# untitled.net
KiCad netlist of a schematic drawn in EAGLE
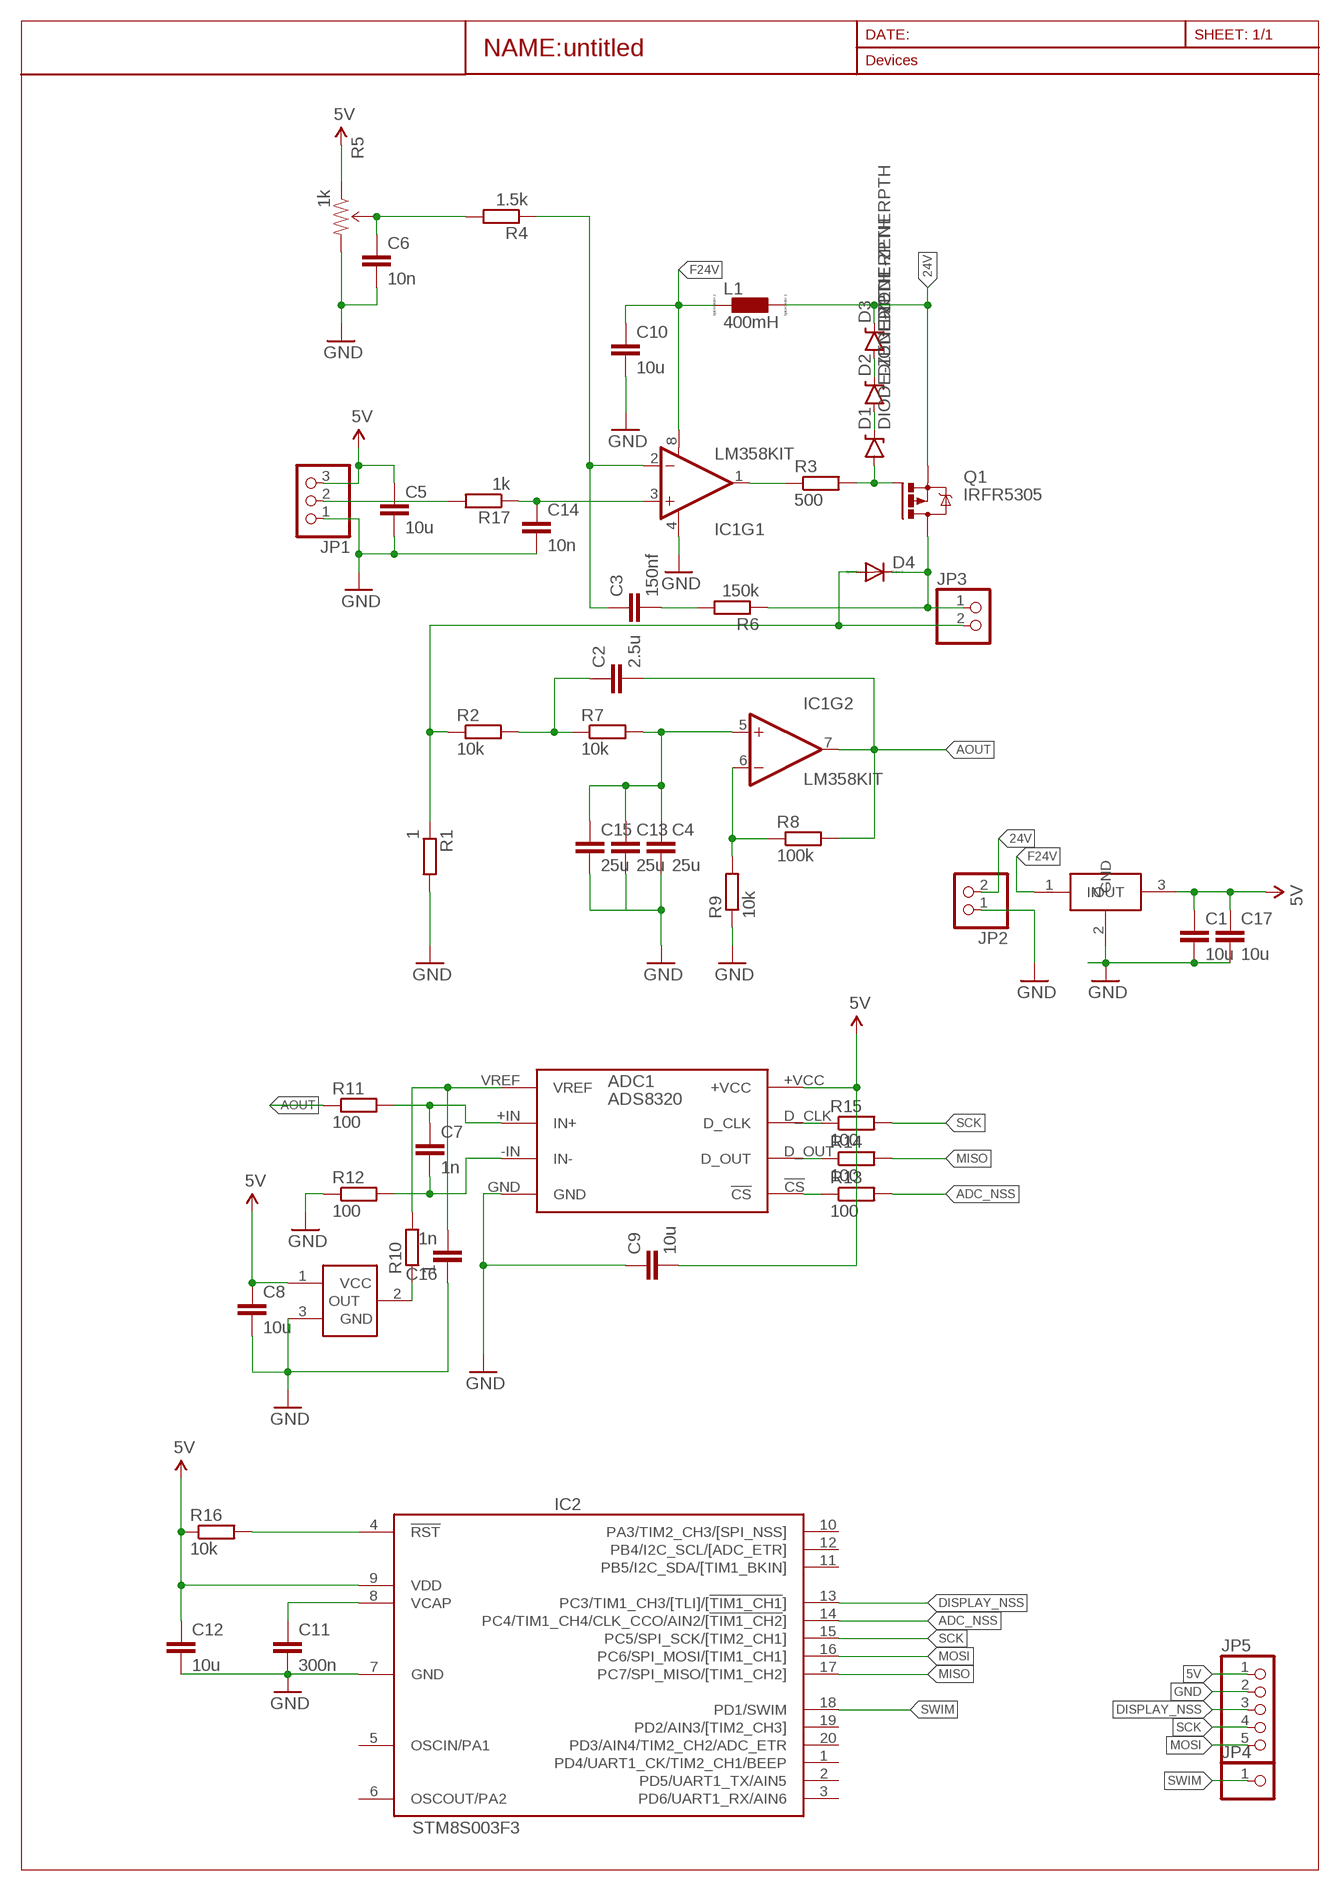
[diagram p0: schematic, sheet 1]

(export (version "E")
  (design (tool "Eeschema 10.0.6"))
  (components
    (comp (ref "ADC1")
      (value "ADS8320")
      (footprint "eagle-import:S-PDSO-G8")
      (libsource (lib "eagle-import") (part "ADS8320"))
    )
    (comp (ref "C1")
      (value "10u")
      (footprint "eagle-import:C0805")
      (libsource (lib "eagle-import") (part "CC0805"))
    )
    (comp (ref "C2")
      (value "2.5u")
      (footprint "eagle-import:C0805")
      (libsource (lib "eagle-import") (part "CC0805"))
    )
    (comp (ref "C3")
      (value "150nf")
      (footprint "eagle-import:C0805")
      (libsource (lib "eagle-import") (part "CC0805"))
    )
    (comp (ref "C4")
      (value "25u")
      (footprint "eagle-import:C0805")
      (libsource (lib "eagle-import") (part "CC0805"))
    )
    (comp (ref "C5")
      (value "10u")
      (footprint "eagle-import:C0805")
      (libsource (lib "eagle-import") (part "CC0805"))
    )
    (comp (ref "C6")
      (value "10n")
      (footprint "eagle-import:C0805")
      (libsource (lib "eagle-import") (part "CC0805"))
    )
    (comp (ref "C7")
      (value "1n")
      (footprint "eagle-import:C0805")
      (libsource (lib "eagle-import") (part "CC0805"))
    )
    (comp (ref "C8")
      (value "10u")
      (footprint "eagle-import:C0805")
      (libsource (lib "eagle-import") (part "CC0805"))
    )
    (comp (ref "C9")
      (value "10u")
      (footprint "eagle-import:C0805")
      (libsource (lib "eagle-import") (part "CC0805"))
    )
    (comp (ref "C10")
      (value "10u")
      (footprint "eagle-import:C0805")
      (libsource (lib "eagle-import") (part "CC0805"))
    )
    (comp (ref "C11")
      (value "300n")
      (footprint "eagle-import:C0805")
      (libsource (lib "eagle-import") (part "CC0805"))
    )
    (comp (ref "C12")
      (value "10u")
      (footprint "eagle-import:C0805")
      (libsource (lib "eagle-import") (part "CC0805"))
    )
    (comp (ref "C13")
      (value "25u")
      (footprint "eagle-import:C0805")
      (libsource (lib "eagle-import") (part "CC0805"))
    )
    (comp (ref "C14")
      (value "10n")
      (footprint "eagle-import:C0805")
      (libsource (lib "eagle-import") (part "CC0805"))
    )
    (comp (ref "C15")
      (value "25u")
      (footprint "eagle-import:C0805")
      (libsource (lib "eagle-import") (part "CC0805"))
    )
    (comp (ref "C16")
      (value "1n")
      (footprint "eagle-import:C0805")
      (libsource (lib "eagle-import") (part "CC0805"))
    )
    (comp (ref "C17")
      (value "10u")
      (footprint "eagle-import:C0805")
      (libsource (lib "eagle-import") (part "CC0805"))
    )
    (comp (ref "D1")
      (value "DIODE-ZENERPTH")
      (footprint "eagle-import:DIODE-ZENER")
      (libsource (lib "eagle-import") (part "DIODE-ZENERPTH"))
    )
    (comp (ref "D2")
      (value "DIODE-ZENERPTH")
      (footprint "eagle-import:DIODE-ZENER")
      (libsource (lib "eagle-import") (part "DIODE-ZENERPTH"))
    )
    (comp (ref "D3")
      (value "DIODE-ZENERPTH")
      (footprint "eagle-import:DIODE-ZENER")
      (libsource (lib "eagle-import") (part "DIODE-ZENERPTH"))
    )
    (comp (ref "D4")
      (value "DIODE-MINIMELF")
      (footprint "eagle-import:MINIMELF")
      (libsource (lib "eagle-import") (part "DIODE-MINIMELF"))
    )
    (comp (ref "IC1")
      (value "LM358KIT")
      (footprint "eagle-import:DIP08-KIT")
      (libsource (lib "eagle-import") (part "LM358KIT"))
    )
    (comp (ref "IC2")
      (value "STM8S003F3")
      (footprint "eagle-import:TSSOP20")
      (libsource (lib "eagle-import") (part "STM8S003F3"))
    )
    (comp (ref "JP1")
      (value "PINHD-1X3")
      (footprint "eagle-import:1X03")
      (libsource (lib "eagle-import") (part "PINHD-1X3"))
    )
    (comp (ref "JP2")
      (value "PINHD-1X02_2.54")
      (footprint "eagle-import:1X02")
      (libsource (lib "eagle-import") (part "PINHD-1X02_2.54"))
    )
    (comp (ref "JP3")
      (value "PINHD-1X02_2.54")
      (footprint "eagle-import:1X02")
      (libsource (lib "eagle-import") (part "PINHD-1X02_2.54"))
    )
    (comp (ref "JP4")
      (value "PINHD-1X01_2.54")
      (footprint "eagle-import:1X01")
      (libsource (lib "eagle-import") (part "PINHD-1X01_2.54"))
    )
    (comp (ref "JP5")
      (value "PINHD-1X05_2.54")
      (footprint "eagle-import:1X05")
      (libsource (lib "eagle-import") (part "PINHD-1X05_2.54"))
    )
    (comp (ref "L1")
      (value "400mH")
      (footprint "eagle-import:L5650M")
      (libsource (lib "eagle-import") (part "LL5650M"))
    )
    (comp (ref "Q1")
      (value "IRFR5305")
      (footprint "eagle-import:D-PAK_TO252AA")
      (libsource (lib "eagle-import") (part "IRF?5305R"))
    )
    (comp (ref "R1")
      (value "1")
      (footprint "eagle-import:R0805")
      (libsource (lib "eagle-import") (part "R0805"))
    )
    (comp (ref "R2")
      (value "10k")
      (footprint "eagle-import:R0805")
      (libsource (lib "eagle-import") (part "R0805"))
    )
    (comp (ref "R3")
      (value "500")
      (footprint "eagle-import:R0805")
      (libsource (lib "eagle-import") (part "R0805"))
    )
    (comp (ref "R4")
      (value "1.5k")
      (footprint "eagle-import:R0805")
      (libsource (lib "eagle-import") (part "R0805"))
    )
    (comp (ref "R5")
      (value "1k")
      (footprint "eagle-import:TRIMPOT_PTH_S3_LOCK")
      (libsource (lib "eagle-import") (part "TRIMPOTTRIMPOT_PTH_S3_LOCK"))
    )
    (comp (ref "R6")
      (value "150k")
      (footprint "eagle-import:R0805")
      (libsource (lib "eagle-import") (part "R0805"))
    )
    (comp (ref "R7")
      (value "10k")
      (footprint "eagle-import:R0805")
      (libsource (lib "eagle-import") (part "R0805"))
    )
    (comp (ref "R8")
      (value "100k")
      (footprint "eagle-import:R0805")
      (libsource (lib "eagle-import") (part "R0805"))
    )
    (comp (ref "R9")
      (value "10k")
      (footprint "eagle-import:R0805")
      (libsource (lib "eagle-import") (part "R0805"))
    )
    (comp (ref "R10")
      (value "1")
      (footprint "eagle-import:R0805")
      (libsource (lib "eagle-import") (part "R0805"))
    )
    (comp (ref "R11")
      (value "100")
      (footprint "eagle-import:R0805")
      (libsource (lib "eagle-import") (part "R0805"))
    )
    (comp (ref "R12")
      (value "100")
      (footprint "eagle-import:R0805")
      (libsource (lib "eagle-import") (part "R0805"))
    )
    (comp (ref "R13")
      (value "100")
      (footprint "eagle-import:R0805")
      (libsource (lib "eagle-import") (part "R0805"))
    )
    (comp (ref "R14")
      (value "100")
      (footprint "eagle-import:R0805")
      (libsource (lib "eagle-import") (part "R0805"))
    )
    (comp (ref "R15")
      (value "100")
      (footprint "eagle-import:R0805")
      (libsource (lib "eagle-import") (part "R0805"))
    )
    (comp (ref "R16")
      (value "10k")
      (footprint "eagle-import:R0805")
      (libsource (lib "eagle-import") (part "R0805"))
    )
    (comp (ref "R17")
      (value "1k")
      (footprint "eagle-import:R0805")
      (libsource (lib "eagle-import") (part "R0805"))
    )
    (comp (ref "U$1")
      (value "REF3025")
      (footprint "eagle-import:SOT23")
      (libsource (lib "eagle-import") (part "REF3025"))
    )
    (comp (ref "U$2")
      (value "L7805C2T")
      (footprint "eagle-import:D2PACK")
      (libsource (lib "eagle-import") (part "L7805C2T"))
    )
  )
  (nets
    (net (code "1") (name "5V") (class "Default")
      (node (ref "ADC1") (pin "+VCC") (pinfunction "+VCC_+VCC") (pintype "power_in"))
      (node (ref "C1") (pin "1") (pinfunction "1_1") (pintype "passive"))
      (node (ref "C12") (pin "1") (pinfunction "1_1") (pintype "passive"))
      (node (ref "C17") (pin "1") (pinfunction "1_1") (pintype "passive"))
      (node (ref "C5") (pin "1") (pinfunction "1_1") (pintype "passive"))
      (node (ref "C8") (pin "1") (pinfunction "1_1") (pintype "passive"))
      (node (ref "C9") (pin "2") (pinfunction "2_2") (pintype "passive"))
      (node (ref "IC2") (pin "9") (pinfunction "VDD_9") (pintype "power_in"))
      (node (ref "JP1") (pin "3") (pinfunction "3_3") (pintype "passive"))
      (node (ref "JP5") (pin "1") (pinfunction "1_1") (pintype "passive"))
      (node (ref "R16") (pin "1") (pinfunction "1_1") (pintype "passive"))
      (node (ref "R5") (pin "1") (pinfunction "CCW_1") (pintype "passive"))
      (node (ref "U$1") (pin "1") (pinfunction "VCC_1") (pintype "bidirectional"))
      (node (ref "U$2") (pin "3") (pinfunction "OUT_3") (pintype "bidirectional"))
    )
    (net (code "2") (name "24V") (class "Default")
      (node (ref "D3") (pin "P$1") (pinfunction "C_P$1") (pintype "passive"))
      (node (ref "JP2") (pin "2") (pinfunction "2_2") (pintype "passive"))
      (node (ref "L1") (pin "1") (pinfunction "1_1") (pintype "passive"))
      (node (ref "Q1") (pin "3") (pinfunction "S_3") (pintype "passive"))
    )
    (net (code "3") (name "ADC_NSS") (class "Default")
      (node (ref "IC2") (pin "14") (pinfunction "PC4/TIM1_CH4/CLK_CCO/AIN2/[~{TIM1_CH2}]_14") (pintype "bidirectional"))
      (node (ref "R13") (pin "2") (pinfunction "2_2") (pintype "passive"))
    )
    (net (code "4") (name "AOUT") (class "Default")
      (node (ref "C2") (pin "2") (pinfunction "2_2") (pintype "passive"))
      (node (ref "IC1") (pin "7") (pinfunction "OUT_7") (pintype "output"))
      (node (ref "R11") (pin "1") (pinfunction "1_1") (pintype "passive"))
      (node (ref "R8") (pin "2") (pinfunction "2_2") (pintype "passive"))
    )
    (net (code "5") (name "DISPLAY_NSS") (class "Default")
      (node (ref "IC2") (pin "13") (pinfunction "PC3/TIM1_CH3/[TLI]/[~{TIM1_CH1}]_13") (pintype "bidirectional"))
      (node (ref "JP5") (pin "3") (pinfunction "3_3") (pintype "passive"))
    )
    (net (code "6") (name "F24V") (class "Default")
      (node (ref "C10") (pin "1") (pinfunction "1_1") (pintype "passive"))
      (node (ref "IC1") (pin "8") (pinfunction "V+_8") (pintype "power_in"))
      (node (ref "L1") (pin "2") (pinfunction "2_2") (pintype "passive"))
      (node (ref "U$2") (pin "1") (pinfunction "IN_1") (pintype "bidirectional"))
    )
    (net (code "7") (name "GND") (class "Default")
      (node (ref "ADC1") (pin "GND") (pinfunction "GND_GND") (pintype "power_in"))
      (node (ref "C1") (pin "2") (pinfunction "2_2") (pintype "passive"))
      (node (ref "C10") (pin "2") (pinfunction "2_2") (pintype "passive"))
      (node (ref "C11") (pin "2") (pinfunction "2_2") (pintype "passive"))
      (node (ref "C12") (pin "2") (pinfunction "2_2") (pintype "passive"))
      (node (ref "C13") (pin "2") (pinfunction "2_2") (pintype "passive"))
      (node (ref "C14") (pin "2") (pinfunction "2_2") (pintype "passive"))
      (node (ref "C15") (pin "2") (pinfunction "2_2") (pintype "passive"))
      (node (ref "C16") (pin "1") (pinfunction "1_1") (pintype "passive"))
      (node (ref "C17") (pin "2") (pinfunction "2_2") (pintype "passive"))
      (node (ref "C4") (pin "2") (pinfunction "2_2") (pintype "passive"))
      (node (ref "C5") (pin "2") (pinfunction "2_2") (pintype "passive"))
      (node (ref "C6") (pin "2") (pinfunction "2_2") (pintype "passive"))
      (node (ref "C8") (pin "2") (pinfunction "2_2") (pintype "passive"))
      (node (ref "C9") (pin "1") (pinfunction "1_1") (pintype "passive"))
      (node (ref "IC1") (pin "4") (pinfunction "V-_4") (pintype "power_in"))
      (node (ref "IC2") (pin "7") (pinfunction "GND_7") (pintype "power_in"))
      (node (ref "JP1") (pin "1") (pinfunction "1_1") (pintype "passive"))
      (node (ref "JP2") (pin "1") (pinfunction "1_1") (pintype "passive"))
      (node (ref "JP5") (pin "2") (pinfunction "2_2") (pintype "passive"))
      (node (ref "R1") (pin "2") (pinfunction "2_2") (pintype "passive"))
      (node (ref "R12") (pin "1") (pinfunction "1_1") (pintype "passive"))
      (node (ref "R5") (pin "3") (pinfunction "CW_3") (pintype "passive"))
      (node (ref "R9") (pin "1") (pinfunction "1_1") (pintype "passive"))
      (node (ref "U$1") (pin "3") (pinfunction "GND_3") (pintype "bidirectional"))
      (node (ref "U$2") (pin "2") (pinfunction "GND_2") (pintype "bidirectional"))
    )
    (net (code "8") (name "MISO") (class "Default")
      (node (ref "IC2") (pin "17") (pinfunction "PC7/SPI_MISO/[TIM1_CH2]_17") (pintype "bidirectional"))
      (node (ref "R14") (pin "2") (pinfunction "2_2") (pintype "passive"))
    )
    (net (code "9") (name "MOSI") (class "Default")
      (node (ref "IC2") (pin "16") (pinfunction "PC6/SPI_MOSI/[TIM1_CH1]_16") (pintype "bidirectional"))
      (node (ref "JP5") (pin "5") (pinfunction "5_5") (pintype "passive"))
    )
    (net (code "10") (name "Net-(ADC1-IN+)") (class "Default")
      (node (ref "ADC1") (pin "+IN") (pinfunction "IN+_+IN") (pintype "input"))
      (node (ref "C7") (pin "1") (pinfunction "1_1") (pintype "passive"))
      (node (ref "R11") (pin "2") (pinfunction "2_2") (pintype "passive"))
    )
    (net (code "11") (name "Net-(ADC1-IN-)") (class "Default")
      (node (ref "ADC1") (pin "-IN") (pinfunction "IN-_-IN") (pintype "input"))
      (node (ref "C7") (pin "2") (pinfunction "2_2") (pintype "passive"))
      (node (ref "R12") (pin "2") (pinfunction "2_2") (pintype "passive"))
    )
    (net (code "12") (name "Net-(ADC1-PadD_CLK)") (class "Default")
      (node (ref "ADC1") (pin "D_CLK") (pinfunction "D_CLK_D_CLK") (pintype "input"))
      (node (ref "R15") (pin "1") (pinfunction "1_1") (pintype "passive"))
    )
    (net (code "13") (name "Net-(ADC1-PadD_OUT)") (class "Default")
      (node (ref "ADC1") (pin "D_OUT") (pinfunction "D_OUT_D_OUT") (pintype "output"))
      (node (ref "R14") (pin "1") (pinfunction "1_1") (pintype "passive"))
    )
    (net (code "14") (name "Net-(ADC1-PadVREF)") (class "Default")
      (node (ref "ADC1") (pin "VREF") (pinfunction "VREF_VREF") (pintype "input"))
      (node (ref "C16") (pin "2") (pinfunction "2_2") (pintype "passive"))
      (node (ref "R10") (pin "2") (pinfunction "2_2") (pintype "passive"))
    )
    (net (code "15") (name "Net-(ADC1-~{CS})") (class "Default")
      (node (ref "ADC1") (pin "!CS") (pinfunction "~{CS}_!CS") (pintype "input"))
      (node (ref "R13") (pin "1") (pinfunction "1_1") (pintype "passive"))
    )
    (net (code "16") (name "Net-(C2-Pad1)") (class "Default")
      (node (ref "C2") (pin "1") (pinfunction "1_1") (pintype "passive"))
      (node (ref "R2") (pin "2") (pinfunction "2_2") (pintype "passive"))
      (node (ref "R7") (pin "1") (pinfunction "1_1") (pintype "passive"))
    )
    (net (code "17") (name "Net-(C3-Pad2)") (class "Default")
      (node (ref "C3") (pin "2") (pinfunction "2_2") (pintype "passive"))
      (node (ref "R6") (pin "2") (pinfunction "2_2") (pintype "passive"))
    )
    (net (code "18") (name "Net-(D1-A)") (class "Default")
      (node (ref "D1") (pin "P$2") (pinfunction "A_P$2") (pintype "passive"))
      (node (ref "Q1") (pin "1") (pinfunction "G_1") (pintype "passive"))
      (node (ref "R3") (pin "2") (pinfunction "2_2") (pintype "passive"))
    )
    (net (code "19") (name "Net-(D1-C)") (class "Default")
      (node (ref "D1") (pin "P$1") (pinfunction "C_P$1") (pintype "passive"))
      (node (ref "D2") (pin "P$2") (pinfunction "A_P$2") (pintype "passive"))
    )
    (net (code "20") (name "Net-(D2-C)") (class "Default")
      (node (ref "D2") (pin "P$1") (pinfunction "C_P$1") (pintype "passive"))
      (node (ref "D3") (pin "P$2") (pinfunction "A_P$2") (pintype "passive"))
    )
    (net (code "21") (name "Net-(D4-PadA)") (class "Default")
      (node (ref "D4") (pin "A") (pinfunction "A_A") (pintype "passive"))
      (node (ref "JP3") (pin "2") (pinfunction "2_2") (pintype "passive"))
      (node (ref "R1") (pin "1") (pinfunction "1_1") (pintype "passive"))
      (node (ref "R2") (pin "1") (pinfunction "1_1") (pintype "passive"))
    )
    (net (code "22") (name "Net-(IC1A-+IN)") (class "Default")
      (node (ref "C14") (pin "1") (pinfunction "1_1") (pintype "passive"))
      (node (ref "IC1") (pin "3") (pinfunction "+IN_3") (pintype "input"))
      (node (ref "R17") (pin "1") (pinfunction "1_1") (pintype "passive"))
    )
    (net (code "23") (name "Net-(IC1A--IN)") (class "Default")
      (node (ref "C3") (pin "1") (pinfunction "1_1") (pintype "passive"))
      (node (ref "IC1") (pin "2") (pinfunction "-IN_2") (pintype "input"))
      (node (ref "R4") (pin "1") (pinfunction "1_1") (pintype "passive"))
    )
    (net (code "24") (name "Net-(IC1A-OUT)") (class "Default")
      (node (ref "IC1") (pin "1") (pinfunction "OUT_1") (pintype "output"))
      (node (ref "R3") (pin "1") (pinfunction "1_1") (pintype "passive"))
    )
    (net (code "25") (name "Net-(IC1B-+IN)") (class "Default")
      (node (ref "C13") (pin "1") (pinfunction "1_1") (pintype "passive"))
      (node (ref "C15") (pin "1") (pinfunction "1_1") (pintype "passive"))
      (node (ref "C4") (pin "1") (pinfunction "1_1") (pintype "passive"))
      (node (ref "IC1") (pin "5") (pinfunction "+IN_5") (pintype "input"))
      (node (ref "R7") (pin "2") (pinfunction "2_2") (pintype "passive"))
    )
    (net (code "26") (name "Net-(IC1B--IN)") (class "Default")
      (node (ref "IC1") (pin "6") (pinfunction "-IN_6") (pintype "input"))
      (node (ref "R8") (pin "1") (pinfunction "1_1") (pintype "passive"))
      (node (ref "R9") (pin "2") (pinfunction "2_2") (pintype "passive"))
    )
    (net (code "27") (name "Net-(IC2-VCAP)") (class "Default")
      (node (ref "C11") (pin "1") (pinfunction "1_1") (pintype "passive"))
      (node (ref "IC2") (pin "8") (pinfunction "VCAP_8") (pintype "power_in"))
    )
    (net (code "28") (name "Net-(IC2-~{RST})") (class "Default")
      (node (ref "IC2") (pin "4") (pinfunction "~{RST}_4") (pintype "input"))
      (node (ref "R16") (pin "2") (pinfunction "2_2") (pintype "passive"))
    )
    (net (code "29") (name "Net-(JP1-Pad2)") (class "Default")
      (node (ref "JP1") (pin "2") (pinfunction "2_2") (pintype "passive"))
      (node (ref "R17") (pin "2") (pinfunction "2_2") (pintype "passive"))
    )
    (net (code "30") (name "Net-(Q1-D)") (class "Default")
      (node (ref "D4") (pin "C") (pinfunction "C_C") (pintype "passive"))
      (node (ref "JP3") (pin "1") (pinfunction "1_1") (pintype "passive"))
      (node (ref "Q1") (pin "4") (pinfunction "D_4") (pintype "passive"))
      (node (ref "R6") (pin "1") (pinfunction "1_1") (pintype "passive"))
    )
    (net (code "31") (name "Net-(R5-WIPER)") (class "Default")
      (node (ref "C6") (pin "1") (pinfunction "1_1") (pintype "passive"))
      (node (ref "R4") (pin "2") (pinfunction "2_2") (pintype "passive"))
      (node (ref "R5") (pin "2") (pinfunction "WIPER_2") (pintype "passive"))
    )
    (net (code "32") (name "Net-(U$1-OUT)") (class "Default")
      (node (ref "R10") (pin "1") (pinfunction "1_1") (pintype "passive"))
      (node (ref "U$1") (pin "2") (pinfunction "OUT_2") (pintype "bidirectional"))
    )
    (net (code "33") (name "SCK") (class "Default")
      (node (ref "IC2") (pin "15") (pinfunction "PC5/SPI_SCK/[TIM2_CH1]_15") (pintype "bidirectional"))
      (node (ref "JP5") (pin "4") (pinfunction "4_4") (pintype "passive"))
      (node (ref "R15") (pin "2") (pinfunction "2_2") (pintype "passive"))
    )
    (net (code "34") (name "SWIM") (class "Default")
      (node (ref "IC2") (pin "18") (pinfunction "PD1/SWIM_18") (pintype "bidirectional"))
      (node (ref "JP4") (pin "1") (pinfunction "1_1") (pintype "passive"))
    )
    (net (code "35") (name "unconnected-(IC2-OSCIN{slash}PA1-Pad5)") (class "Default")
      (node (ref "IC2") (pin "5") (pinfunction "OSCIN/PA1_5") (pintype "bidirectional"))
    )
    (net (code "36") (name "unconnected-(IC2-OSCOUT{slash}PA2-Pad6)") (class "Default")
      (node (ref "IC2") (pin "6") (pinfunction "OSCOUT/PA2_6") (pintype "bidirectional"))
    )
    (net (code "37") (name "unconnected-(IC2-PA3{slash}TIM2_CH3{slash}[SPI_NSS]-Pad10)") (class "Default")
      (node (ref "IC2") (pin "10") (pinfunction "PA3/TIM2_CH3/[SPI_NSS]_10") (pintype "bidirectional"))
    )
    (net (code "38") (name "unconnected-(IC2-PB4{slash}I2C_SCL{slash}[ADC_ETR]-Pad12)") (class "Default")
      (node (ref "IC2") (pin "12") (pinfunction "PB4/I2C_SCL/[ADC_ETR]_12") (pintype "bidirectional"))
    )
    (net (code "39") (name "unconnected-(IC2-PB5{slash}I2C_SDA{slash}[TIM1_BKIN]-Pad11)") (class "Default")
      (node (ref "IC2") (pin "11") (pinfunction "PB5/I2C_SDA/[TIM1_BKIN]_11") (pintype "bidirectional"))
    )
    (net (code "40") (name "unconnected-(IC2-PD2{slash}AIN3{slash}[TIM2_CH3]-Pad19)") (class "Default")
      (node (ref "IC2") (pin "19") (pinfunction "PD2/AIN3/[TIM2_CH3]_19") (pintype "bidirectional"))
    )
    (net (code "41") (name "unconnected-(IC2-PD3{slash}AIN4{slash}TIM2_CH2{slash}ADC_ETR-Pad20)") (class "Default")
      (node (ref "IC2") (pin "20") (pinfunction "PD3/AIN4/TIM2_CH2/ADC_ETR_20") (pintype "bidirectional"))
    )
    (net (code "42") (name "unconnected-(IC2-PD4{slash}UART1_CK{slash}TIM2_CH1{slash}BEEP-Pad1)") (class "Default")
      (node (ref "IC2") (pin "1") (pinfunction "PD4/UART1_CK/TIM2_CH1/BEEP_1") (pintype "bidirectional"))
    )
    (net (code "43") (name "unconnected-(IC2-PD5{slash}UART1_TX{slash}AIN5-Pad2)") (class "Default")
      (node (ref "IC2") (pin "2") (pinfunction "PD5/UART1_TX/AIN5_2") (pintype "bidirectional"))
    )
    (net (code "44") (name "unconnected-(IC2-PD6{slash}UART1_RX{slash}AIN6-Pad3)") (class "Default")
      (node (ref "IC2") (pin "3") (pinfunction "PD6/UART1_RX/AIN6_3") (pintype "bidirectional"))
    )
  )
)
